# 188_93_EC_15.net
KiCad netlist of a schematic drawn in EAGLE
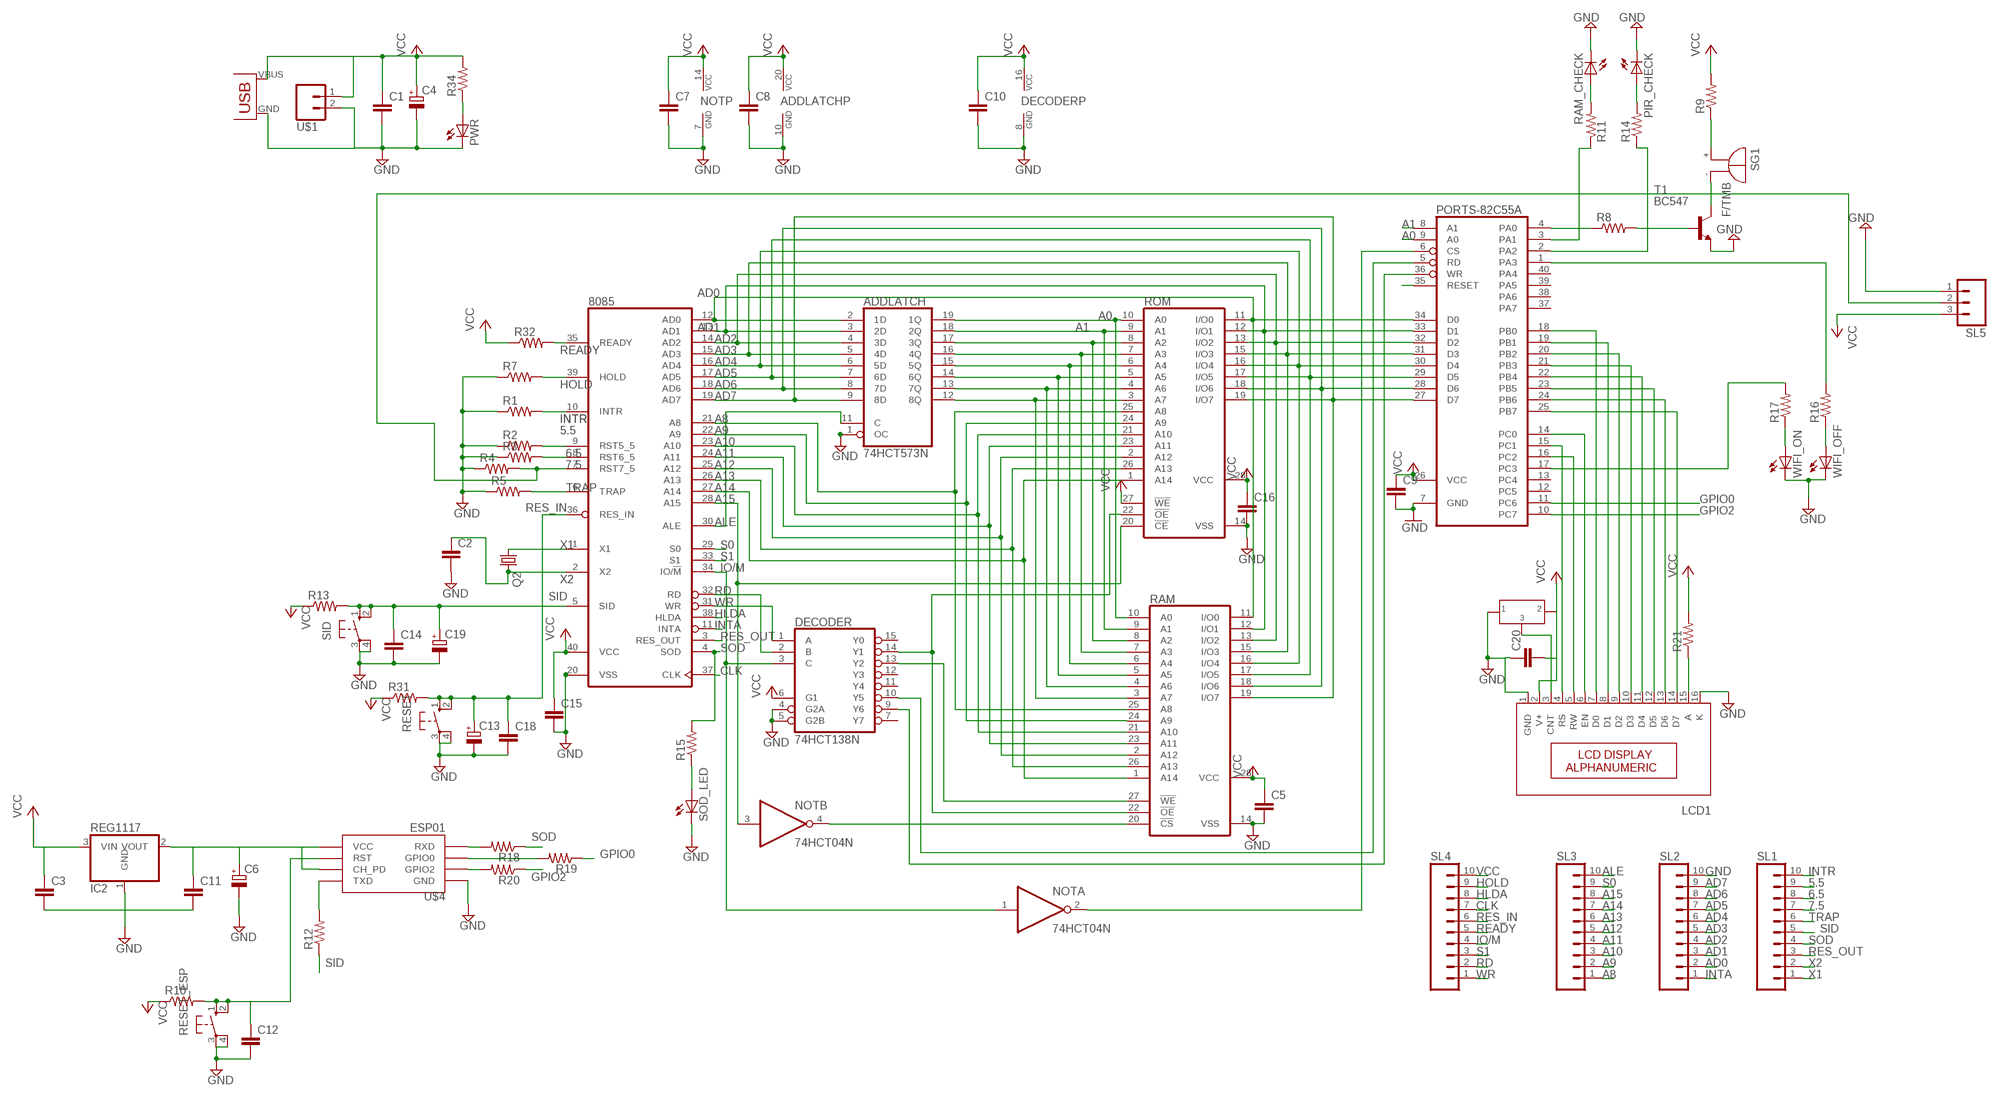
[diagram p0: schematic, sheet 1]

(export (version "E")
  (design (tool "Eeschema 10.0.6"))
  (components
    (comp (ref "8085")
      (value "8085")
      (footprint "eagle-import:DIL40")
      (libsource (lib "eagle-import") (part "8085"))
    )
    (comp (ref "ADDLATCH")
      (value "74HCT573N")
      (footprint "eagle-import:DIL20")
      (libsource (lib "eagle-import") (part "74573NHCT"))
    )
    (comp (ref "C1")
      (value "C-EU025-024X044")
      (footprint "eagle-import:C025-024X044")
      (libsource (lib "eagle-import") (part "C-EU025-024X044"))
    )
    (comp (ref "C2")
      (value "C-EU025-024X044")
      (footprint "eagle-import:C025-024X044")
      (libsource (lib "eagle-import") (part "C-EU025-024X044"))
    )
    (comp (ref "C3")
      (value "C-EU025-024X044")
      (footprint "eagle-import:C025-024X044")
      (libsource (lib "eagle-import") (part "C-EU025-024X044"))
    )
    (comp (ref "C4")
      (value "CPOL-EUE5-8.5")
      (footprint "eagle-import:E5-8,5")
      (libsource (lib "eagle-import") (part "CPOL-EUE5-8.5"))
    )
    (comp (ref "C5")
      (value "C-EU025-024X044")
      (footprint "eagle-import:C025-024X044")
      (libsource (lib "eagle-import") (part "C-EU025-024X044"))
    )
    (comp (ref "C6")
      (value "CPOL-EUE5-8.5")
      (footprint "eagle-import:E5-8,5")
      (libsource (lib "eagle-import") (part "CPOL-EUE5-8.5"))
    )
    (comp (ref "C7")
      (value "C-EU025-024X044")
      (footprint "eagle-import:C025-024X044")
      (libsource (lib "eagle-import") (part "C-EU025-024X044"))
    )
    (comp (ref "C8")
      (value "C-EU025-024X044")
      (footprint "eagle-import:C025-024X044")
      (libsource (lib "eagle-import") (part "C-EU025-024X044"))
    )
    (comp (ref "C9")
      (value "C-EU025-024X044")
      (footprint "eagle-import:C025-024X044")
      (libsource (lib "eagle-import") (part "C-EU025-024X044"))
    )
    (comp (ref "C10")
      (value "C-EU025-024X044")
      (footprint "eagle-import:C025-024X044")
      (libsource (lib "eagle-import") (part "C-EU025-024X044"))
    )
    (comp (ref "C11")
      (value "C-EU025-024X044")
      (footprint "eagle-import:C025-024X044")
      (libsource (lib "eagle-import") (part "C-EU025-024X044"))
    )
    (comp (ref "C12")
      (value "C-EU025-024X044")
      (footprint "eagle-import:C025-024X044")
      (libsource (lib "eagle-import") (part "C-EU025-024X044"))
    )
    (comp (ref "C13")
      (value "CPOL-EUE5-8.5")
      (footprint "eagle-import:E5-8,5")
      (libsource (lib "eagle-import") (part "CPOL-EUE5-8.5"))
    )
    (comp (ref "C14")
      (value "C-EU025-024X044")
      (footprint "eagle-import:C025-024X044")
      (libsource (lib "eagle-import") (part "C-EU025-024X044"))
    )
    (comp (ref "C15")
      (value "C-EU025-024X044")
      (footprint "eagle-import:C025-024X044")
      (libsource (lib "eagle-import") (part "C-EU025-024X044"))
    )
    (comp (ref "C16")
      (value "C-EU025-024X044")
      (footprint "eagle-import:C025-024X044")
      (libsource (lib "eagle-import") (part "C-EU025-024X044"))
    )
    (comp (ref "C18")
      (value "C-EU025-024X044")
      (footprint "eagle-import:C025-024X044")
      (libsource (lib "eagle-import") (part "C-EU025-024X044"))
    )
    (comp (ref "C19")
      (value "CPOL-EUE5-8.5")
      (footprint "eagle-import:E5-8,5")
      (libsource (lib "eagle-import") (part "CPOL-EUE5-8.5"))
    )
    (comp (ref "C20")
      (value "C-EU025-024X044")
      (footprint "eagle-import:C025-024X044")
      (libsource (lib "eagle-import") (part "C-EU025-024X044"))
    )
    (comp (ref "DECODER")
      (value "74HCT138N")
      (footprint "eagle-import:DIL16")
      (libsource (lib "eagle-import") (part "74138NHCT"))
    )
    (comp (ref "IC2")
      (value "REG1117")
      (footprint "eagle-import:SOT223")
      (libsource (lib "eagle-import") (part "REG1117"))
    )
    (comp (ref "LCD1")
      (value "16X2LCD")
      (footprint "eagle-import:16X2_LCD")
      (libsource (lib "eagle-import") (part "16X2LCD"))
    )
    (comp (ref "NOT")
      (value "74HCT04N")
      (footprint "eagle-import:DIL14")
      (libsource (lib "eagle-import") (part "7404NHCT"))
    )
    (comp (ref "PIR_CHECK")
      (value "LED5MM")
      (footprint "eagle-import:LED5MM")
      (libsource (lib "eagle-import") (part "LED5MM"))
    )
    (comp (ref "PORTS-82C55A")
      (value "82C55A")
      (footprint "eagle-import:DIL40")
      (fields (field (name "MF") "INTERSIL") (field (name "MPN") "IP82C55AZ"))
      (libsource (lib "eagle-import") (part "82C55A"))
    )
    (comp (ref "PWR")
      (value "LED5MM")
      (footprint "eagle-import:LED5MM")
      (libsource (lib "eagle-import") (part "LED5MM"))
    )
    (comp (ref "Q2")
      (value "CRYSTALHC49US")
      (footprint "eagle-import:HC49US")
      (libsource (lib "eagle-import") (part "CRYSTALHC49US"))
    )
    (comp (ref "R1")
      (value "R-US_0207/7")
      (footprint "eagle-import:0207_7")
      (libsource (lib "eagle-import") (part "R-US_0207/7"))
    )
    (comp (ref "R2")
      (value "R-US_0207/7")
      (footprint "eagle-import:0207_7")
      (libsource (lib "eagle-import") (part "R-US_0207/7"))
    )
    (comp (ref "R3")
      (value "R-US_0207/7")
      (footprint "eagle-import:0207_7")
      (libsource (lib "eagle-import") (part "R-US_0207/7"))
    )
    (comp (ref "R4")
      (value "R-US_0207/7")
      (footprint "eagle-import:0207_7")
      (libsource (lib "eagle-import") (part "R-US_0207/7"))
    )
    (comp (ref "R5")
      (value "R-US_0207/7")
      (footprint "eagle-import:0207_7")
      (libsource (lib "eagle-import") (part "R-US_0207/7"))
    )
    (comp (ref "R6")
      (value "PRESET_LR")
      (footprint "eagle-import:PRESET_LR")
      (libsource (lib "eagle-import") (part "PRESET_LR"))
    )
    (comp (ref "R7")
      (value "R-US_0207/7")
      (footprint "eagle-import:0207_7")
      (libsource (lib "eagle-import") (part "R-US_0207/7"))
    )
    (comp (ref "R8")
      (value "R-US_0207/7")
      (footprint "eagle-import:0207_7")
      (libsource (lib "eagle-import") (part "R-US_0207/7"))
    )
    (comp (ref "R9")
      (value "R-US_0207/7")
      (footprint "eagle-import:0207_7")
      (libsource (lib "eagle-import") (part "R-US_0207/7"))
    )
    (comp (ref "R10")
      (value "R-US_0207/7")
      (footprint "eagle-import:0207_7")
      (libsource (lib "eagle-import") (part "R-US_0207/7"))
    )
    (comp (ref "R11")
      (value "R-US_0207/7")
      (footprint "eagle-import:0207_7")
      (libsource (lib "eagle-import") (part "R-US_0207/7"))
    )
    (comp (ref "R12")
      (value "R-US_0207/7")
      (footprint "eagle-import:0207_7")
      (libsource (lib "eagle-import") (part "R-US_0207/7"))
    )
    (comp (ref "R13")
      (value "R-US_0207/7")
      (footprint "eagle-import:0207_7")
      (libsource (lib "eagle-import") (part "R-US_0207/7"))
    )
    (comp (ref "R14")
      (value "R-US_0207/7")
      (footprint "eagle-import:0207_7")
      (libsource (lib "eagle-import") (part "R-US_0207/7"))
    )
    (comp (ref "R15")
      (value "R-US_0207/7")
      (footprint "eagle-import:0207_7")
      (libsource (lib "eagle-import") (part "R-US_0207/7"))
    )
    (comp (ref "R16")
      (value "R-US_0207/7")
      (footprint "eagle-import:0207_7")
      (libsource (lib "eagle-import") (part "R-US_0207/7"))
    )
    (comp (ref "R17")
      (value "R-US_0207/7")
      (footprint "eagle-import:0207_7")
      (libsource (lib "eagle-import") (part "R-US_0207/7"))
    )
    (comp (ref "R18")
      (value "R-US_0207/7")
      (footprint "eagle-import:0207_7")
      (libsource (lib "eagle-import") (part "R-US_0207/7"))
    )
    (comp (ref "R19")
      (value "R-US_0207/7")
      (footprint "eagle-import:0207_7")
      (libsource (lib "eagle-import") (part "R-US_0207/7"))
    )
    (comp (ref "R20")
      (value "R-US_0207/7")
      (footprint "eagle-import:0207_7")
      (libsource (lib "eagle-import") (part "R-US_0207/7"))
    )
    (comp (ref "R21")
      (value "R-US_0207/7")
      (footprint "eagle-import:0207_7")
      (libsource (lib "eagle-import") (part "R-US_0207/7"))
    )
    (comp (ref "R31")
      (value "R-US_0207/7")
      (footprint "eagle-import:0207_7")
      (libsource (lib "eagle-import") (part "R-US_0207/7"))
    )
    (comp (ref "R32")
      (value "R-US_0207/7")
      (footprint "eagle-import:0207_7")
      (libsource (lib "eagle-import") (part "R-US_0207/7"))
    )
    (comp (ref "R34")
      (value "R-US_0207/7")
      (footprint "eagle-import:0207_7")
      (libsource (lib "eagle-import") (part "R-US_0207/7"))
    )
    (comp (ref "RAM")
      (value "62256P")
      (footprint "eagle-import:DIL28-6")
      (libsource (lib "eagle-import") (part "62256P"))
    )
    (comp (ref "RAM_CHECK")
      (value "LED5MM")
      (footprint "eagle-import:LED5MM")
      (libsource (lib "eagle-import") (part "LED5MM"))
    )
    (comp (ref "RESET")
      (value "10-XX")
      (footprint "eagle-import:B3F-10XX")
      (libsource (lib "eagle-import") (part "10-XX"))
    )
    (comp (ref "RESET_ESP")
      (value "10-XX")
      (footprint "eagle-import:B3F-10XX")
      (libsource (lib "eagle-import") (part "10-XX"))
    )
    (comp (ref "ROM")
      (value "58C256P")
      (footprint "eagle-import:DIL28-6")
      (fields (field (name "MPN") "HN58C256AP85E"))
      (libsource (lib "eagle-import") (part "58C256P"))
    )
    (comp (ref "SG1")
      (value "F/TMB")
      (footprint "eagle-import:F_TMB")
      (libsource (lib "eagle-import") (part "F/TMB"))
    )
    (comp (ref "SID")
      (value "10-XX")
      (footprint "eagle-import:B3F-10XX")
      (libsource (lib "eagle-import") (part "10-XX"))
    )
    (comp (ref "SL1")
      (value "M10")
      (footprint "eagle-import:10P")
      (libsource (lib "eagle-import") (part "M10"))
    )
    (comp (ref "SL2")
      (value "M10")
      (footprint "eagle-import:10P")
      (libsource (lib "eagle-import") (part "M10"))
    )
    (comp (ref "SL3")
      (value "M10")
      (footprint "eagle-import:10P")
      (libsource (lib "eagle-import") (part "M10"))
    )
    (comp (ref "SL4")
      (value "M10")
      (footprint "eagle-import:10P")
      (libsource (lib "eagle-import") (part "M10"))
    )
    (comp (ref "SL5")
      (value "M03")
      (footprint "eagle-import:03P")
      (libsource (lib "eagle-import") (part "M03"))
    )
    (comp (ref "SOD_LED")
      (value "LED5MM")
      (footprint "eagle-import:LED5MM")
      (libsource (lib "eagle-import") (part "LED5MM"))
    )
    (comp (ref "T1")
      (value "BC547")
      (footprint "eagle-import:TO92")
      (libsource (lib "eagle-import") (part "BC547"))
    )
    (comp (ref "U$1")
      (value "M02")
      (footprint "eagle-import:02P")
      (libsource (lib "eagle-import") (part "M02"))
    )
    (comp (ref "U$2")
      (value "USB(POWER)")
      (footprint "eagle-import:USB(POWER)")
      (libsource (lib "eagle-import") (part "USB(POWER)"))
    )
    (comp (ref "U$4")
      (value "ESP01")
      (footprint "eagle-import:ESP01")
      (libsource (lib "eagle-import") (part "ESP01"))
    )
    (comp (ref "WIFI_OFF")
      (value "LED5MM")
      (footprint "eagle-import:LED5MM")
      (libsource (lib "eagle-import") (part "LED5MM"))
    )
    (comp (ref "WIFI_ON")
      (value "LED5MM")
      (footprint "eagle-import:LED5MM")
      (libsource (lib "eagle-import") (part "LED5MM"))
    )
  )
  (nets
    (net (code "1") (name "/5.5") (class "Default")
      (node (ref "8085") (pin "9") (pinfunction "RST5_5_9") (pintype "input"))
      (node (ref "R2") (pin "2") (pinfunction "2_2") (pintype "passive"))
      (node (ref "SL1") (pin "9") (pinfunction "9_9") (pintype "passive"))
    )
    (net (code "2") (name "/6.5") (class "Default")
      (node (ref "8085") (pin "8") (pinfunction "RST6_5_8") (pintype "input"))
      (node (ref "R3") (pin "2") (pinfunction "2_2") (pintype "passive"))
      (node (ref "SL1") (pin "8") (pinfunction "8_8") (pintype "passive"))
    )
    (net (code "3") (name "/7.5") (class "Default")
      (node (ref "8085") (pin "7") (pinfunction "RST7_5_7") (pintype "input"))
      (node (ref "R4") (pin "2") (pinfunction "2_2") (pintype "passive"))
      (node (ref "SL1") (pin "7") (pinfunction "7_7") (pintype "passive"))
      (node (ref "SL5") (pin "2") (pinfunction "2_2") (pintype "passive"))
    )
    (net (code "4") (name "/A0") (class "Default")
      (node (ref "ADDLATCH") (pin "19") (pinfunction "1Q_19") (pintype "tri_state"))
      (node (ref "PORTS-82C55A") (pin "9") (pinfunction "A0_9") (pintype "input"))
      (node (ref "RAM") (pin "10") (pinfunction "A0_10") (pintype "input"))
      (node (ref "ROM") (pin "10") (pinfunction "A0_10") (pintype "input"))
    )
    (net (code "5") (name "/A1") (class "Default")
      (node (ref "ADDLATCH") (pin "18") (pinfunction "2Q_18") (pintype "tri_state"))
      (node (ref "PORTS-82C55A") (pin "8") (pinfunction "A1_8") (pintype "input"))
      (node (ref "RAM") (pin "9") (pinfunction "A1_9") (pintype "input"))
      (node (ref "ROM") (pin "9") (pinfunction "A1_9") (pintype "input"))
    )
    (net (code "6") (name "/A8") (class "Default")
      (node (ref "8085") (pin "21") (pinfunction "A8_21") (pintype "output"))
      (node (ref "RAM") (pin "25") (pinfunction "A8_25") (pintype "input"))
      (node (ref "ROM") (pin "25") (pinfunction "A8_25") (pintype "input"))
      (node (ref "SL3") (pin "1") (pinfunction "1_1") (pintype "passive"))
    )
    (net (code "7") (name "/A9") (class "Default")
      (node (ref "8085") (pin "22") (pinfunction "A9_22") (pintype "output"))
      (node (ref "RAM") (pin "24") (pinfunction "A9_24") (pintype "input"))
      (node (ref "ROM") (pin "24") (pinfunction "A9_24") (pintype "input"))
      (node (ref "SL3") (pin "2") (pinfunction "2_2") (pintype "passive"))
    )
    (net (code "8") (name "/A10") (class "Default")
      (node (ref "8085") (pin "23") (pinfunction "A10_23") (pintype "output"))
      (node (ref "RAM") (pin "21") (pinfunction "A10_21") (pintype "input"))
      (node (ref "ROM") (pin "21") (pinfunction "A10_21") (pintype "input"))
      (node (ref "SL3") (pin "3") (pinfunction "3_3") (pintype "passive"))
    )
    (net (code "9") (name "/A11") (class "Default")
      (node (ref "8085") (pin "24") (pinfunction "A11_24") (pintype "output"))
      (node (ref "RAM") (pin "23") (pinfunction "A11_23") (pintype "input"))
      (node (ref "ROM") (pin "23") (pinfunction "A11_23") (pintype "input"))
      (node (ref "SL3") (pin "4") (pinfunction "4_4") (pintype "passive"))
    )
    (net (code "10") (name "/A12") (class "Default")
      (node (ref "8085") (pin "25") (pinfunction "A12_25") (pintype "output"))
      (node (ref "RAM") (pin "2") (pinfunction "A12_2") (pintype "input"))
      (node (ref "ROM") (pin "2") (pinfunction "A12_2") (pintype "input"))
      (node (ref "SL3") (pin "5") (pinfunction "5_5") (pintype "passive"))
    )
    (net (code "11") (name "/A13") (class "Default")
      (node (ref "8085") (pin "26") (pinfunction "A13_26") (pintype "output"))
      (node (ref "RAM") (pin "26") (pinfunction "A13_26") (pintype "input"))
      (node (ref "ROM") (pin "26") (pinfunction "A13_26") (pintype "input"))
      (node (ref "SL3") (pin "6") (pinfunction "6_6") (pintype "passive"))
    )
    (net (code "12") (name "/A14") (class "Default")
      (node (ref "8085") (pin "27") (pinfunction "A14_27") (pintype "output"))
      (node (ref "RAM") (pin "1") (pinfunction "A14_1") (pintype "input"))
      (node (ref "ROM") (pin "1") (pinfunction "A14_1") (pintype "input"))
      (node (ref "SL3") (pin "7") (pinfunction "7_7") (pintype "passive"))
    )
    (net (code "13") (name "/A15") (class "Default")
      (node (ref "8085") (pin "28") (pinfunction "A15_28") (pintype "output"))
      (node (ref "NOT") (pin "3") (pinfunction "I_3") (pintype "input"))
      (node (ref "ROM") (pin "20") (pinfunction "~{CE}_20") (pintype "input"))
      (node (ref "SL3") (pin "8") (pinfunction "8_8") (pintype "passive"))
    )
    (net (code "14") (name "/AD0") (class "Default")
      (node (ref "8085") (pin "12") (pinfunction "AD0_12") (pintype "bidirectional"))
      (node (ref "ADDLATCH") (pin "2") (pinfunction "1D_2") (pintype "input"))
      (node (ref "PORTS-82C55A") (pin "34") (pinfunction "D0_34") (pintype "bidirectional"))
      (node (ref "RAM") (pin "11") (pinfunction "I/O0_11") (pintype "bidirectional"))
      (node (ref "ROM") (pin "11") (pinfunction "I/O0_11") (pintype "tri_state"))
      (node (ref "SL2") (pin "2") (pinfunction "2_2") (pintype "passive"))
    )
    (net (code "15") (name "/AD1") (class "Default")
      (node (ref "8085") (pin "13") (pinfunction "AD1_13") (pintype "bidirectional"))
      (node (ref "ADDLATCH") (pin "3") (pinfunction "2D_3") (pintype "input"))
      (node (ref "PORTS-82C55A") (pin "33") (pinfunction "D1_33") (pintype "bidirectional"))
      (node (ref "RAM") (pin "12") (pinfunction "I/O1_12") (pintype "bidirectional"))
      (node (ref "ROM") (pin "12") (pinfunction "I/O1_12") (pintype "tri_state"))
      (node (ref "SL2") (pin "3") (pinfunction "3_3") (pintype "passive"))
    )
    (net (code "16") (name "/AD2") (class "Default")
      (node (ref "8085") (pin "14") (pinfunction "AD2_14") (pintype "bidirectional"))
      (node (ref "ADDLATCH") (pin "4") (pinfunction "3D_4") (pintype "input"))
      (node (ref "PORTS-82C55A") (pin "32") (pinfunction "D2_32") (pintype "bidirectional"))
      (node (ref "RAM") (pin "13") (pinfunction "I/O2_13") (pintype "bidirectional"))
      (node (ref "ROM") (pin "13") (pinfunction "I/O2_13") (pintype "tri_state"))
      (node (ref "SL2") (pin "4") (pinfunction "4_4") (pintype "passive"))
    )
    (net (code "17") (name "/AD3") (class "Default")
      (node (ref "8085") (pin "15") (pinfunction "AD3_15") (pintype "bidirectional"))
      (node (ref "ADDLATCH") (pin "5") (pinfunction "4D_5") (pintype "input"))
      (node (ref "PORTS-82C55A") (pin "31") (pinfunction "D3_31") (pintype "bidirectional"))
      (node (ref "RAM") (pin "15") (pinfunction "I/O3_15") (pintype "bidirectional"))
      (node (ref "ROM") (pin "15") (pinfunction "I/O3_15") (pintype "tri_state"))
      (node (ref "SL2") (pin "5") (pinfunction "5_5") (pintype "passive"))
    )
    (net (code "18") (name "/AD4") (class "Default")
      (node (ref "8085") (pin "16") (pinfunction "AD4_16") (pintype "bidirectional"))
      (node (ref "ADDLATCH") (pin "6") (pinfunction "5D_6") (pintype "input"))
      (node (ref "PORTS-82C55A") (pin "30") (pinfunction "D4_30") (pintype "bidirectional"))
      (node (ref "RAM") (pin "16") (pinfunction "I/O4_16") (pintype "bidirectional"))
      (node (ref "ROM") (pin "16") (pinfunction "I/O4_16") (pintype "tri_state"))
      (node (ref "SL2") (pin "6") (pinfunction "6_6") (pintype "passive"))
    )
    (net (code "19") (name "/AD5") (class "Default")
      (node (ref "8085") (pin "17") (pinfunction "AD5_17") (pintype "bidirectional"))
      (node (ref "ADDLATCH") (pin "7") (pinfunction "6D_7") (pintype "input"))
      (node (ref "PORTS-82C55A") (pin "29") (pinfunction "D5_29") (pintype "bidirectional"))
      (node (ref "RAM") (pin "17") (pinfunction "I/O5_17") (pintype "bidirectional"))
      (node (ref "ROM") (pin "17") (pinfunction "I/O5_17") (pintype "tri_state"))
      (node (ref "SL2") (pin "7") (pinfunction "7_7") (pintype "passive"))
    )
    (net (code "20") (name "/AD6") (class "Default")
      (node (ref "8085") (pin "18") (pinfunction "AD6_18") (pintype "bidirectional"))
      (node (ref "ADDLATCH") (pin "8") (pinfunction "7D_8") (pintype "input"))
      (node (ref "PORTS-82C55A") (pin "28") (pinfunction "D6_28") (pintype "bidirectional"))
      (node (ref "RAM") (pin "18") (pinfunction "I/O6_18") (pintype "bidirectional"))
      (node (ref "ROM") (pin "18") (pinfunction "I/O6_18") (pintype "tri_state"))
      (node (ref "SL2") (pin "8") (pinfunction "8_8") (pintype "passive"))
    )
    (net (code "21") (name "/AD7") (class "Default")
      (node (ref "8085") (pin "19") (pinfunction "AD7_19") (pintype "bidirectional"))
      (node (ref "ADDLATCH") (pin "9") (pinfunction "8D_9") (pintype "input"))
      (node (ref "PORTS-82C55A") (pin "27") (pinfunction "D7_27") (pintype "bidirectional"))
      (node (ref "RAM") (pin "19") (pinfunction "I/O7_19") (pintype "bidirectional"))
      (node (ref "ROM") (pin "19") (pinfunction "I/O7_19") (pintype "tri_state"))
      (node (ref "SL2") (pin "9") (pinfunction "9_9") (pintype "passive"))
    )
    (net (code "22") (name "/ALE") (class "Default")
      (node (ref "8085") (pin "30") (pinfunction "ALE_30") (pintype "output"))
      (node (ref "ADDLATCH") (pin "11") (pinfunction "C_11") (pintype "input"))
      (node (ref "SL3") (pin "10") (pinfunction "10_10") (pintype "passive"))
    )
    (net (code "23") (name "/CLK") (class "Default")
      (node (ref "8085") (pin "37") (pinfunction "CLK_37") (pintype "output"))
      (node (ref "SL4") (pin "7") (pinfunction "7_7") (pintype "passive"))
    )
    (net (code "24") (name "/GPIO0") (class "Default")
      (node (ref "PORTS-82C55A") (pin "11") (pinfunction "PC6_11") (pintype "bidirectional"))
      (node (ref "R19") (pin "1") (pinfunction "1_1") (pintype "passive"))
    )
    (net (code "25") (name "/GPIO2") (class "Default")
      (node (ref "PORTS-82C55A") (pin "10") (pinfunction "PC7_10") (pintype "bidirectional"))
      (node (ref "R20") (pin "1") (pinfunction "1_1") (pintype "passive"))
    )
    (net (code "26") (name "/HLDA") (class "Default")
      (node (ref "8085") (pin "38") (pinfunction "HLDA_38") (pintype "output"))
      (node (ref "SL4") (pin "8") (pinfunction "8_8") (pintype "passive"))
    )
    (net (code "27") (name "/HOLD") (class "Default")
      (node (ref "8085") (pin "39") (pinfunction "HOLD_39") (pintype "input"))
      (node (ref "R7") (pin "2") (pinfunction "2_2") (pintype "passive"))
      (node (ref "SL4") (pin "9") (pinfunction "9_9") (pintype "passive"))
    )
    (net (code "28") (name "/INTA") (class "Default")
      (node (ref "8085") (pin "11") (pinfunction "INTA_11") (pintype "output"))
      (node (ref "SL2") (pin "1") (pinfunction "1_1") (pintype "passive"))
    )
    (net (code "29") (name "/INTR") (class "Default")
      (node (ref "8085") (pin "10") (pinfunction "INTR_10") (pintype "input"))
      (node (ref "R1") (pin "2") (pinfunction "2_2") (pintype "passive"))
      (node (ref "SL1") (pin "10") (pinfunction "10_10") (pintype "passive"))
    )
    (net (code "30") (name "/IO{slash}M") (class "Default")
      (node (ref "8085") (pin "34") (pinfunction "IO/~{M}_34") (pintype "output"))
      (node (ref "DECODER") (pin "3") (pinfunction "C_3") (pintype "input"))
      (node (ref "NOT") (pin "1") (pinfunction "I_1") (pintype "input"))
      (node (ref "SL4") (pin "4") (pinfunction "4_4") (pintype "passive"))
    )
    (net (code "31") (name "/RD") (class "Default")
      (node (ref "8085") (pin "32") (pinfunction "RD_32") (pintype "output"))
      (node (ref "DECODER") (pin "2") (pinfunction "B_2") (pintype "input"))
      (node (ref "SL4") (pin "2") (pinfunction "2_2") (pintype "passive"))
    )
    (net (code "32") (name "/READY") (class "Default")
      (node (ref "8085") (pin "35") (pinfunction "READY_35") (pintype "input"))
      (node (ref "R32") (pin "2") (pinfunction "2_2") (pintype "passive"))
      (node (ref "SL4") (pin "5") (pinfunction "5_5") (pintype "passive"))
    )
    (net (code "33") (name "/RES_IN") (class "Default")
      (node (ref "8085") (pin "36") (pinfunction "RES_IN_36") (pintype "input"))
      (node (ref "C13") (pin "+") (pinfunction "+_+") (pintype "passive"))
      (node (ref "C18") (pin "1") (pinfunction "1_1") (pintype "passive"))
      (node (ref "R31") (pin "2") (pinfunction "2_2") (pintype "passive"))
      (node (ref "RESET") (pin "1") (pinfunction "S_1") (pintype "passive"))
      (node (ref "RESET") (pin "2") (pinfunction "S1_2") (pintype "passive"))
      (node (ref "SL4") (pin "6") (pinfunction "6_6") (pintype "passive"))
    )
    (net (code "34") (name "/RES_OUT") (class "Default")
      (node (ref "8085") (pin "3") (pinfunction "RES_OUT_3") (pintype "output"))
      (node (ref "PORTS-82C55A") (pin "35") (pinfunction "RESET_35") (pintype "input"))
      (node (ref "SL1") (pin "3") (pinfunction "3_3") (pintype "passive"))
    )
    (net (code "35") (name "/S0") (class "Default")
      (node (ref "8085") (pin "29") (pinfunction "S0_29") (pintype "output"))
      (node (ref "SL3") (pin "9") (pinfunction "9_9") (pintype "passive"))
    )
    (net (code "36") (name "/S1") (class "Default")
      (node (ref "8085") (pin "33") (pinfunction "S1_33") (pintype "output"))
      (node (ref "SL4") (pin "3") (pinfunction "3_3") (pintype "passive"))
    )
    (net (code "37") (name "/SID") (class "Default")
      (node (ref "8085") (pin "5") (pinfunction "SID_5") (pintype "input"))
      (node (ref "C14") (pin "1") (pinfunction "1_1") (pintype "passive"))
      (node (ref "C19") (pin "+") (pinfunction "+_+") (pintype "passive"))
      (node (ref "R12") (pin "1") (pinfunction "1_1") (pintype "passive"))
      (node (ref "R13") (pin "2") (pinfunction "2_2") (pintype "passive"))
      (node (ref "SID") (pin "1") (pinfunction "S_1") (pintype "passive"))
      (node (ref "SID") (pin "2") (pinfunction "S1_2") (pintype "passive"))
      (node (ref "SL1") (pin "5") (pinfunction "5_5") (pintype "passive"))
    )
    (net (code "38") (name "/SOD") (class "Default")
      (node (ref "8085") (pin "4") (pinfunction "SOD_4") (pintype "output"))
      (node (ref "R15") (pin "2") (pinfunction "2_2") (pintype "passive"))
      (node (ref "R18") (pin "1") (pinfunction "1_1") (pintype "passive"))
      (node (ref "SL1") (pin "4") (pinfunction "4_4") (pintype "passive"))
    )
    (net (code "39") (name "/TRAP") (class "Default")
      (node (ref "8085") (pin "6") (pinfunction "TRAP_6") (pintype "input"))
      (node (ref "R5") (pin "2") (pinfunction "2_2") (pintype "passive"))
      (node (ref "SL1") (pin "6") (pinfunction "6_6") (pintype "passive"))
    )
    (net (code "40") (name "/WR") (class "Default")
      (node (ref "8085") (pin "31") (pinfunction "WR_31") (pintype "output"))
      (node (ref "DECODER") (pin "1") (pinfunction "A_1") (pintype "input"))
      (node (ref "SL4") (pin "1") (pinfunction "1_1") (pintype "passive"))
    )
    (net (code "41") (name "/X1") (class "Default")
      (node (ref "8085") (pin "1") (pinfunction "X1_1") (pintype "input"))
      (node (ref "Q2") (pin "1") (pinfunction "1_1") (pintype "passive"))
      (node (ref "SL1") (pin "1") (pinfunction "1_1") (pintype "passive"))
    )
    (net (code "42") (name "/X2") (class "Default")
      (node (ref "8085") (pin "2") (pinfunction "X2_2") (pintype "input"))
      (node (ref "C2") (pin "1") (pinfunction "1_1") (pintype "passive"))
      (node (ref "Q2") (pin "2") (pinfunction "2_2") (pintype "passive"))
      (node (ref "SL1") (pin "2") (pinfunction "2_2") (pintype "passive"))
    )
    (net (code "43") (name "GND") (class "Default")
      (node (ref "8085") (pin "20") (pinfunction "VSS_20") (pintype "power_in"))
      (node (ref "ADDLATCH") (pin "1") (pinfunction "OC_1") (pintype "input"))
      (node (ref "ADDLATCH") (pin "10") (pinfunction "GND_10") (pintype "power_in"))
      (node (ref "C1") (pin "2") (pinfunction "2_2") (pintype "passive"))
      (node (ref "C10") (pin "2") (pinfunction "2_2") (pintype "passive"))
      (node (ref "C11") (pin "2") (pinfunction "2_2") (pintype "passive"))
      (node (ref "C12") (pin "2") (pinfunction "2_2") (pintype "passive"))
      (node (ref "C13") (pin "-") (pinfunction "-_-") (pintype "passive"))
      (node (ref "C14") (pin "2") (pinfunction "2_2") (pintype "passive"))
      (node (ref "C15") (pin "2") (pinfunction "2_2") (pintype "passive"))
      (node (ref "C16") (pin "2") (pinfunction "2_2") (pintype "passive"))
      (node (ref "C18") (pin "2") (pinfunction "2_2") (pintype "passive"))
      (node (ref "C19") (pin "-") (pinfunction "-_-") (pintype "passive"))
      (node (ref "C2") (pin "2") (pinfunction "2_2") (pintype "passive"))
      (node (ref "C20") (pin "1") (pinfunction "1_1") (pintype "passive"))
      (node (ref "C3") (pin "2") (pinfunction "2_2") (pintype "passive"))
      (node (ref "C4") (pin "-") (pinfunction "-_-") (pintype "passive"))
      (node (ref "C5") (pin "2") (pinfunction "2_2") (pintype "passive"))
      (node (ref "C6") (pin "-") (pinfunction "-_-") (pintype "passive"))
      (node (ref "C7") (pin "2") (pinfunction "2_2") (pintype "passive"))
      (node (ref "C8") (pin "2") (pinfunction "2_2") (pintype "passive"))
      (node (ref "C9") (pin "2") (pinfunction "2_2") (pintype "passive"))
      (node (ref "DECODER") (pin "4") (pinfunction "G2A_4") (pintype "input"))
      (node (ref "DECODER") (pin "5") (pinfunction "G2B_5") (pintype "input"))
      (node (ref "DECODER") (pin "8") (pinfunction "GND_8") (pintype "power_in"))
      (node (ref "IC2") (pin "1") (pinfunction "GND_1") (pintype "power_in"))
      (node (ref "LCD1") (pin "1") (pinfunction "GND_1") (pintype "bidirectional"))
      (node (ref "LCD1") (pin "16") (pinfunction "K_16") (pintype "bidirectional"))
      (node (ref "NOT") (pin "7") (pinfunction "GND_7") (pintype "power_in"))
      (node (ref "PIR_CHECK") (pin "K") (pinfunction "C_K") (pintype "passive"))
      (node (ref "PORTS-82C55A") (pin "7") (pinfunction "GND_7") (pintype "power_in"))
      (node (ref "PWR") (pin "K") (pinfunction "C_K") (pintype "passive"))
      (node (ref "R1") (pin "1") (pinfunction "1_1") (pintype "passive"))
      (node (ref "R2") (pin "1") (pinfunction "1_1") (pintype "passive"))
      (node (ref "R3") (pin "1") (pinfunction "1_1") (pintype "passive"))
      (node (ref "R4") (pin "1") (pinfunction "1_1") (pintype "passive"))
      (node (ref "R5") (pin "1") (pinfunction "1_1") (pintype "passive"))
      (node (ref "R6") (pin "P$1") (pinfunction "1_P$1") (pintype "passive"))
      (node (ref "R7") (pin "1") (pinfunction "1_1") (pintype "passive"))
      (node (ref "RAM") (pin "14") (pinfunction "VSS_14") (pintype "power_in"))
      (node (ref "RAM_CHECK") (pin "K") (pinfunction "C_K") (pintype "passive"))
      (node (ref "RESET") (pin "3") (pinfunction "P_3") (pintype "passive"))
      (node (ref "RESET") (pin "4") (pinfunction "P1_4") (pintype "passive"))
      (node (ref "RESET_ESP") (pin "3") (pinfunction "P_3") (pintype "passive"))
      (node (ref "RESET_ESP") (pin "4") (pinfunction "P1_4") (pintype "passive"))
      (node (ref "ROM") (pin "14") (pinfunction "VSS_14") (pintype "power_in"))
      (node (ref "SID") (pin "3") (pinfunction "P_3") (pintype "passive"))
      (node (ref "SID") (pin "4") (pinfunction "P1_4") (pintype "passive"))
      (node (ref "SL2") (pin "10") (pinfunction "10_10") (pintype "passive"))
      (node (ref "SL5") (pin "1") (pinfunction "1_1") (pintype "passive"))
      (node (ref "SOD_LED") (pin "K") (pinfunction "C_K") (pintype "passive"))
      (node (ref "T1") (pin "1") (pinfunction "E_1") (pintype "passive"))
      (node (ref "U$1") (pin "2") (pinfunction "2_2") (pintype "passive"))
      (node (ref "U$2") (pin "GND") (pinfunction "GND_GND") (pintype "power_in"))
      (node (ref "U$4") (pin "GND") (pinfunction "GND_GND") (pintype "bidirectional"))
      (node (ref "WIFI_OFF") (pin "K") (pinfunction "C_K") (pintype "passive"))
      (node (ref "WIFI_ON") (pin "K") (pinfunction "C_K") (pintype "passive"))
    )
    (net (code "44") (name "Net-(ADDLATCHA-3Q)") (class "Default")
      (node (ref "ADDLATCH") (pin "17") (pinfunction "3Q_17") (pintype "tri_state"))
      (node (ref "RAM") (pin "8") (pinfunction "A2_8") (pintype "input"))
      (node (ref "ROM") (pin "8") (pinfunction "A2_8") (pintype "input"))
    )
    (net (code "45") (name "Net-(ADDLATCHA-4Q)") (class "Default")
      (node (ref "ADDLATCH") (pin "16") (pinfunction "4Q_16") (pintype "tri_state"))
      (node (ref "RAM") (pin "7") (pinfunction "A3_7") (pintype "input"))
      (node (ref "ROM") (pin "7") (pinfunction "A3_7") (pintype "input"))
    )
    (net (code "46") (name "Net-(ADDLATCHA-5Q)") (class "Default")
      (node (ref "ADDLATCH") (pin "15") (pinfunction "5Q_15") (pintype "tri_state"))
      (node (ref "RAM") (pin "6") (pinfunction "A4_6") (pintype "input"))
      (node (ref "ROM") (pin "6") (pinfunction "A4_6") (pintype "input"))
    )
    (net (code "47") (name "Net-(ADDLATCHA-6Q)") (class "Default")
      (node (ref "ADDLATCH") (pin "14") (pinfunction "6Q_14") (pintype "tri_state"))
      (node (ref "RAM") (pin "5") (pinfunction "A5_5") (pintype "input"))
      (node (ref "ROM") (pin "5") (pinfunction "A5_5") (pintype "input"))
    )
    (net (code "48") (name "Net-(ADDLATCHA-7Q)") (class "Default")
      (node (ref "ADDLATCH") (pin "13") (pinfunction "7Q_13") (pintype "tri_state"))
      (node (ref "RAM") (pin "4") (pinfunction "A6_4") (pintype "input"))
      (node (ref "ROM") (pin "4") (pinfunction "A6_4") (pintype "input"))
    )
    (net (code "49") (name "Net-(ADDLATCHA-8Q)") (class "Default")
      (node (ref "ADDLATCH") (pin "12") (pinfunction "8Q_12") (pintype "tri_state"))
      (node (ref "RAM") (pin "3") (pinfunction "A7_3") (pintype "input"))
      (node (ref "ROM") (pin "3") (pinfunction "A7_3") (pintype "input"))
    )
    (net (code "50") (name "Net-(DECODERA-Y1)") (class "Default")
      (node (ref "DECODER") (pin "14") (pinfunction "Y1_14") (pintype "output"))
      (node (ref "RAM") (pin "22") (pinfunction "~{OE}_22") (pintype "input"))
      (node (ref "ROM") (pin "22") (pinfunction "~{OE}_22") (pintype "input"))
    )
    (net (code "51") (name "Net-(DECODERA-Y2)") (class "Default")
      (node (ref "DECODER") (pin "13") (pinfunction "Y2_13") (pintype "output"))
      (node (ref "RAM") (pin "27") (pinfunction "~{WE}_27") (pintype "input"))
    )
    (net (code "52") (name "Net-(DECODERA-Y5)") (class "Default")
      (node (ref "DECODER") (pin "10") (pinfunction "Y5_10") (pintype "output"))
      (node (ref "PORTS-82C55A") (pin "5") (pinfunction "RD_5") (pintype "input"))
    )
    (net (code "53") (name "Net-(DECODERA-Y6)") (class "Default")
      (node (ref "DECODER") (pin "9") (pinfunction "Y6_9") (pintype "output"))
      (node (ref "PORTS-82C55A") (pin "36") (pinfunction "WR_36") (pintype "input"))
    )
    (net (code "54") (name "Net-(IC2-VOUT)") (class "Default")
      (node (ref "C11") (pin "1") (pinfunction "1_1") (pintype "passive"))
      (node (ref "C6") (pin "+") (pinfunction "+_+") (pintype "passive"))
      (node (ref "IC2") (pin "2") (pinfunction "VOUT_2") (pintype "output"))
      (node (ref "U$4") (pin "CH_PD") (pinfunction "CH_PD_CH_PD") (pintype "bidirectional"))
      (node (ref "U$4") (pin "VCC") (pinfunction "VCC_VCC") (pintype "bidirectional"))
    )
    (net (code "55") (name "Net-(LCD1-A)") (class "Default")
      (node (ref "LCD1") (pin "15") (pinfunction "A_15") (pintype "bidirectional"))
      (node (ref "R21") (pin "1") (pinfunction "1_1") (pintype "passive"))
    )
    (net (code "56") (name "Net-(LCD1-CNT)") (class "Default")
      (node (ref "LCD1") (pin "3") (pinfunction "CNT_3") (pintype "bidirectional"))
      (node (ref "R6") (pin "P$3") (pinfunction "3_P$3") (pintype "passive"))
    )
    (net (code "57") (name "Net-(LCD1-D0)") (class "Default")
      (node (ref "LCD1") (pin "7") (pinfunction "D0_7") (pintype "bidirectional"))
      (node (ref "PORTS-82C55A") (pin "18") (pinfunction "PB0_18") (pintype "bidirectional"))
    )
    (net (code "58") (name "Net-(LCD1-D1)") (class "Default")
      (node (ref "LCD1") (pin "8") (pinfunction "D1_8") (pintype "bidirectional"))
      (node (ref "PORTS-82C55A") (pin "19") (pinfunction "PB1_19") (pintype "bidirectional"))
    )
    (net (code "59") (name "Net-(LCD1-D2)") (class "Default")
      (node (ref "LCD1") (pin "9") (pinfunction "D2_9") (pintype "bidirectional"))
      (node (ref "PORTS-82C55A") (pin "20") (pinfunction "PB2_20") (pintype "bidirectional"))
    )
    (net (code "60") (name "Net-(LCD1-D3)") (class "Default")
      (node (ref "LCD1") (pin "10") (pinfunction "D3_10") (pintype "bidirectional"))
      (node (ref "PORTS-82C55A") (pin "21") (pinfunction "PB3_21") (pintype "bidirectional"))
    )
    (net (code "61") (name "Net-(LCD1-D4)") (class "Default")
      (node (ref "LCD1") (pin "11") (pinfunction "D4_11") (pintype "bidirectional"))
      (node (ref "PORTS-82C55A") (pin "22") (pinfunction "PB4_22") (pintype "bidirectional"))
    )
    (net (code "62") (name "Net-(LCD1-D5)") (class "Default")
      (node (ref "LCD1") (pin "12") (pinfunction "D5_12") (pintype "bidirectional"))
      (node (ref "PORTS-82C55A") (pin "23") (pinfunction "PB5_23") (pintype "bidirectional"))
    )
    (net (code "63") (name "Net-(LCD1-D6)") (class "Default")
      (node (ref "LCD1") (pin "13") (pinfunction "D6_13") (pintype "bidirectional"))
      (node (ref "PORTS-82C55A") (pin "24") (pinfunction "PB6_24") (pintype "bidirectional"))
    )
    (net (code "64") (name "Net-(LCD1-D7)") (class "Default")
      (node (ref "LCD1") (pin "14") (pinfunction "D7_14") (pintype "bidirectional"))
      (node (ref "PORTS-82C55A") (pin "25") (pinfunction "PB7_25") (pintype "bidirectional"))
    )
    (net (code "65") (name "Net-(LCD1-EN)") (class "Default")
      (node (ref "LCD1") (pin "6") (pinfunction "EN_6") (pintype "bidirectional"))
      (node (ref "PORTS-82C55A") (pin "14") (pinfunction "PC0_14") (pintype "bidirectional"))
    )
    (net (code "66") (name "Net-(LCD1-RS)") (class "Default")
      (node (ref "LCD1") (pin "4") (pinfunction "RS_4") (pintype "bidirectional"))
      (node (ref "PORTS-82C55A") (pin "15") (pinfunction "PC1_15") (pintype "bidirectional"))
    )
    (net (code "67") (name "Net-(LCD1-RW)") (class "Default")
      (node (ref "LCD1") (pin "5") (pinfunction "RW_5") (pintype "bidirectional"))
      (node (ref "PORTS-82C55A") (pin "16") (pinfunction "PC2_16") (pintype "bidirectional"))
    )
    (net (code "68") (name "Net-(NOTA-O)") (class "Default")
      (node (ref "NOT") (pin "2") (pinfunction "O_2") (pintype "output"))
      (node (ref "PORTS-82C55A") (pin "6") (pinfunction "CS_6") (pintype "input"))
    )
    (net (code "69") (name "Net-(NOTB-O)") (class "Default")
      (node (ref "NOT") (pin "4") (pinfunction "O_4") (pintype "output"))
      (node (ref "RAM") (pin "20") (pinfunction "~{CS}_20") (pintype "input"))
    )
    (net (code "70") (name "Net-(PIR_CHECK-PadA)") (class "Default")
      (node (ref "PIR_CHECK") (pin "A") (pinfunction "A_A") (pintype "passive"))
      (node (ref "R14") (pin "2") (pinfunction "2_2") (pintype "passive"))
    )
    (net (code "71") (name "Net-(PORTS-82C55A-PA0)") (class "Default")
      (node (ref "PORTS-82C55A") (pin "4") (pinfunction "PA0_4") (pintype "bidirectional"))
      (node (ref "R8") (pin "1") (pinfunction "1_1") (pintype "passive"))
    )
    (net (code "72") (name "Net-(PORTS-82C55A-PA1)") (class "Default")
      (node (ref "PORTS-82C55A") (pin "3") (pinfunction "PA1_3") (pintype "bidirectional"))
      (node (ref "R11") (pin "1") (pinfunction "1_1") (pintype "passive"))
    )
    (net (code "73") (name "Net-(PORTS-82C55A-PA2)") (class "Default")
      (node (ref "PORTS-82C55A") (pin "2") (pinfunction "PA2_2") (pintype "bidirectional"))
      (node (ref "R14") (pin "1") (pinfunction "1_1") (pintype "passive"))
    )
    (net (code "74") (name "Net-(PORTS-82C55A-PA3)") (class "Default")
      (node (ref "PORTS-82C55A") (pin "1") (pinfunction "PA3_1") (pintype "bidirectional"))
      (node (ref "R16") (pin "2") (pinfunction "2_2") (pintype "passive"))
    )
    (net (code "75") (name "Net-(PORTS-82C55A-PC3)") (class "Default")
      (node (ref "PORTS-82C55A") (pin "17") (pinfunction "PC3_17") (pintype "bidirectional"))
      (node (ref "R17") (pin "2") (pinfunction "2_2") (pintype "passive"))
    )
    (net (code "76") (name "Net-(PWR-PadA)") (class "Default")
      (node (ref "PWR") (pin "A") (pinfunction "A_A") (pintype "passive"))
      (node (ref "R34") (pin "1") (pinfunction "1_1") (pintype "passive"))
    )
    (net (code "77") (name "Net-(R9-Pad1)") (class "Default")
      (node (ref "R9") (pin "1") (pinfunction "1_1") (pintype "passive"))
      (node (ref "SG1") (pin "+") (pinfunction "+_+") (pintype "passive"))
    )
    (net (code "78") (name "Net-(R11-Pad2)") (class "Default")
      (node (ref "R11") (pin "2") (pinfunction "2_2") (pintype "passive"))
      (node (ref "RAM_CHECK") (pin "A") (pinfunction "A_A") (pintype "passive"))
    )
    (net (code "79") (name "Net-(R15-Pad1)") (class "Default")
      (node (ref "R15") (pin "1") (pinfunction "1_1") (pintype "passive"))
      (node (ref "SOD_LED") (pin "A") (pinfunction "A_A") (pintype "passive"))
    )
    (net (code "80") (name "Net-(R16-Pad1)") (class "Default")
      (node (ref "R16") (pin "1") (pinfunction "1_1") (pintype "passive"))
      (node (ref "WIFI_OFF") (pin "A") (pinfunction "A_A") (pintype "passive"))
    )
    (net (code "81") (name "Net-(R17-Pad1)") (class "Default")
      (node (ref "R17") (pin "1") (pinfunction "1_1") (pintype "passive"))
      (node (ref "WIFI_ON") (pin "A") (pinfunction "A_A") (pintype "passive"))
    )
    (net (code "82") (name "Net-(R19-Pad2)") (class "Default")
      (node (ref "R19") (pin "2") (pinfunction "2_2") (pintype "passive"))
      (node (ref "U$4") (pin "GPIO0") (pinfunction "GPIO0_GPIO0") (pintype "bidirectional"))
    )
    (net (code "83") (name "Net-(R20-Pad2)") (class "Default")
      (node (ref "R20") (pin "2") (pinfunction "2_2") (pintype "passive"))
      (node (ref "U$4") (pin "GPIO2") (pinfunction "GPIO2_GPIO2") (pintype "bidirectional"))
    )
    (net (code "84") (name "Net-(RESET_ESP-S)") (class "Default")
      (node (ref "C12") (pin "1") (pinfunction "1_1") (pintype "passive"))
      (node (ref "R10") (pin "2") (pinfunction "2_2") (pintype "passive"))
      (node (ref "RESET_ESP") (pin "1") (pinfunction "S_1") (pintype "passive"))
      (node (ref "RESET_ESP") (pin "2") (pinfunction "S1_2") (pintype "passive"))
      (node (ref "U$4") (pin "RST") (pinfunction "RST_RST") (pintype "bidirectional"))
    )
    (net (code "85") (name "Net-(T1-B)") (class "Default")
      (node (ref "R8") (pin "2") (pinfunction "2_2") (pintype "passive"))
      (node (ref "T1") (pin "2") (pinfunction "B_2") (pintype "passive"))
    )
    (net (code "86") (name "Net-(T1-C)") (class "Default")
      (node (ref "SG1") (pin "-") (pinfunction "-_-") (pintype "passive"))
      (node (ref "T1") (pin "3") (pinfunction "C_3") (pintype "passive"))
    )
    (net (code "87") (name "Net-(U$4-RXD)") (class "Default")
      (node (ref "R18") (pin "2") (pinfunction "2_2") (pintype "passive"))
      (node (ref "U$4") (pin "RX") (pinfunction "RXD_RX") (pintype "bidirectional"))
    )
    (net (code "88") (name "Net-(U$4-TXD)") (class "Default")
      (node (ref "R12") (pin "2") (pinfunction "2_2") (pintype "passive"))
      (node (ref "U$4") (pin "TX") (pinfunction "TXD_TX") (pintype "bidirectional"))
    )
    (net (code "89") (name "VCC") (class "Default")
      (node (ref "8085") (pin "40") (pinfunction "VCC_40") (pintype "power_in"))
      (node (ref "ADDLATCH") (pin "20") (pinfunction "VCC_20") (pintype "power_in"))
      (node (ref "C1") (pin "1") (pinfunction "1_1") (pintype "passive"))
      (node (ref "C10") (pin "1") (pinfunction "1_1") (pintype "passive"))
      (node (ref "C15") (pin "1") (pinfunction "1_1") (pintype "passive"))
      (node (ref "C16") (pin "1") (pinfunction "1_1") (pintype "passive"))
      (node (ref "C20") (pin "2") (pinfunction "2_2") (pintype "passive"))
      (node (ref "C3") (pin "1") (pinfunction "1_1") (pintype "passive"))
      (node (ref "C4") (pin "+") (pinfunction "+_+") (pintype "passive"))
      (node (ref "C5") (pin "1") (pinfunction "1_1") (pintype "passive"))
      (node (ref "C7") (pin "1") (pinfunction "1_1") (pintype "passive"))
      (node (ref "C8") (pin "1") (pinfunction "1_1") (pintype "passive"))
      (node (ref "C9") (pin "1") (pinfunction "1_1") (pintype "passive"))
      (node (ref "DECODER") (pin "16") (pinfunction "VCC_16") (pintype "power_in"))
      (node (ref "DECODER") (pin "6") (pinfunction "G1_6") (pintype "input"))
      (node (ref "IC2") (pin "3") (pinfunction "VIN_3") (pintype "input"))
      (node (ref "LCD1") (pin "2") (pinfunction "V+_2") (pintype "bidirectional"))
      (node (ref "NOT") (pin "14") (pinfunction "VCC_14") (pintype "power_in"))
      (node (ref "PORTS-82C55A") (pin "26") (pinfunction "VCC_26") (pintype "power_in"))
      (node (ref "R10") (pin "1") (pinfunction "1_1") (pintype "passive"))
      (node (ref "R13") (pin "1") (pinfunction "1_1") (pintype "passive"))
      (node (ref "R21") (pin "2") (pinfunction "2_2") (pintype "passive"))
      (node (ref "R31") (pin "1") (pinfunction "1_1") (pintype "passive"))
      (node (ref "R32") (pin "1") (pinfunction "1_1") (pintype "passive"))
      (node (ref "R34") (pin "2") (pinfunction "2_2") (pintype "passive"))
      (node (ref "R6") (pin "P$2") (pinfunction "2_P$2") (pintype "passive"))
      (node (ref "R9") (pin "2") (pinfunction "2_2") (pintype "passive"))
      (node (ref "RAM") (pin "28") (pinfunction "VCC_28") (pintype "power_in"))
      (node (ref "ROM") (pin "27") (pinfunction "~{WE}_27") (pintype "input"))
      (node (ref "ROM") (pin "28") (pinfunction "VCC_28") (pintype "power_in"))
      (node (ref "SL4") (pin "10") (pinfunction "10_10") (pintype "passive"))
      (node (ref "SL5") (pin "3") (pinfunction "3_3") (pintype "passive"))
      (node (ref "U$1") (pin "1") (pinfunction "1_1") (pintype "passive"))
      (node (ref "U$2") (pin "VBUS") (pinfunction "VCC_VBUS") (pintype "power_in"))
    )
    (net (code "90") (name "unconnected-(DECODERA-Y0-Pad15)") (class "Default")
      (node (ref "DECODER") (pin "15") (pinfunction "Y0_15") (pintype "output"))
    )
    (net (code "91") (name "unconnected-(DECODERA-Y3-Pad12)") (class "Default")
      (node (ref "DECODER") (pin "12") (pinfunction "Y3_12") (pintype "output"))
    )
    (net (code "92") (name "unconnected-(DECODERA-Y4-Pad11)") (class "Default")
      (node (ref "DECODER") (pin "11") (pinfunction "Y4_11") (pintype "output"))
    )
    (net (code "93") (name "unconnected-(DECODERA-Y7-Pad7)") (class "Default")
      (node (ref "DECODER") (pin "7") (pinfunction "Y7_7") (pintype "output"))
    )
    (net (code "94") (name "unconnected-(PORTS-82C55A-PA4-Pad40)") (class "Default")
      (node (ref "PORTS-82C55A") (pin "40") (pinfunction "PA4_40") (pintype "bidirectional"))
    )
    (net (code "95") (name "unconnected-(PORTS-82C55A-PA5-Pad39)") (class "Default")
      (node (ref "PORTS-82C55A") (pin "39") (pinfunction "PA5_39") (pintype "bidirectional"))
    )
    (net (code "96") (name "unconnected-(PORTS-82C55A-PA6-Pad38)") (class "Default")
      (node (ref "PORTS-82C55A") (pin "38") (pinfunction "PA6_38") (pintype "bidirectional"))
    )
    (net (code "97") (name "unconnected-(PORTS-82C55A-PA7-Pad37)") (class "Default")
      (node (ref "PORTS-82C55A") (pin "37") (pinfunction "PA7_37") (pintype "bidirectional"))
    )
    (net (code "98") (name "unconnected-(PORTS-82C55A-PC4-Pad13)") (class "Default")
      (node (ref "PORTS-82C55A") (pin "13") (pinfunction "PC4_13") (pintype "bidirectional"))
    )
    (net (code "99") (name "unconnected-(PORTS-82C55A-PC5-Pad12)") (class "Default")
      (node (ref "PORTS-82C55A") (pin "12") (pinfunction "PC5_12") (pintype "bidirectional"))
    )
  )
)
